# AC_Relay.net
KiCad netlist of a schematic drawn in Altium Designer
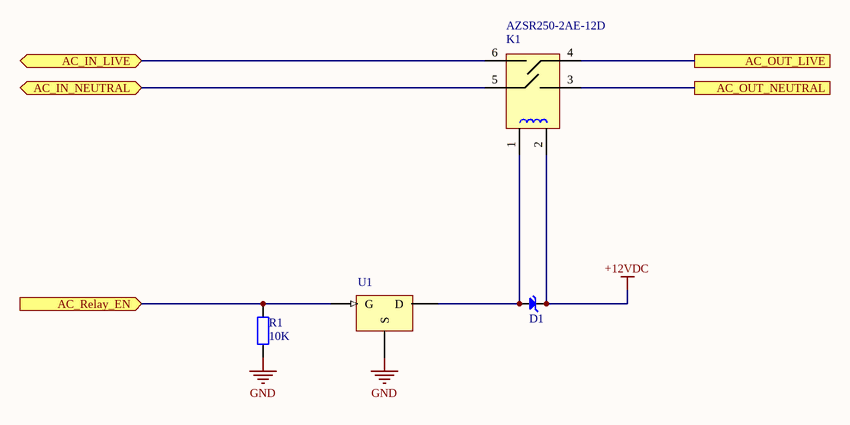
[diagram p0: AC_Relay.SchDoc]

(export (version "E")
  (design (tool "Eeschema 10.0.6"))
  (components
    (comp (ref "D1")
      (value "SMF16A")
      (footprint "SOD-123H")
      (description "Zener Diode")
      (fields (field (name "VOLTAGE") "16V") (field (name "MANUFACTURER") "Littelfuse Inc."))
      (libsource (lib "Database_library") (part "Zener_Diode"))
    )
    (comp (ref "K1")
      (value "AZSR250-2AE-12D")
      (footprint "AZSR250")
      (fields (field (name "MANUFACTURER") "American Zettler"))
      (libsource (lib "Database_library") (part "AZSR250"))
    )
    (comp (ref "R1")
      (value "10K")
      (footprint "RES 0603/1608")
      (description "RES SMD 10K OHM 1% 1/10W 0603")
      (fields (field (name "PART NUMBER") "RC0603FR-0710KL") (field (name "TOLERANCE") "±1%"))
      (libsource (lib "electric_racing_lib") (part "Resistor"))
    )
    (comp (ref "U1")
      (value "SZNUD3112LT1G")
      (footprint "SZNUD3112LT1G")
      (fields
        (field (name "PARTNUMBER") "SZNUD3112LT1GOSCT-ND")
        (field (name "MANUFACTURER") "ON Semiconductor")
      )
      (libsource (lib "Database_library") (part "SZNUD3112LT1G"))
    )
  )
  (nets
    (net (code "1") (name "+12VDC") (class "Default")
      (node (ref "D1") (pin "K") (pinfunction "K_K") (pintype "passive"))
      (node (ref "K1") (pin "2") (pintype "passive"))
    )
    (net (code "2") (name "/AC_IN_LIVE") (class "Default") (node (ref "K1") (pin "6") (pintype "passive")))
    (net (code "3") (name "/AC_IN_NEUTRAL") (class "Default") (node (ref "K1") (pin "5") (pintype "passive")))
    (net (code "4") (name "/AC_OUT_LIVE") (class "Default") (node (ref "K1") (pin "4") (pintype "passive")))
    (net (code "5") (name "/AC_OUT_NEUTRAL") (class "Default")
      (node (ref "K1") (pin "3") (pintype "passive"))
    )
    (net (code "6") (name "/AC_Relay_EN") (class "Default")
      (node (ref "R1") (pin "2") (pinfunction "2_2") (pintype "passive"))
      (node (ref "U1") (pin "1") (pinfunction "G_1") (pintype "input"))
    )
    (net (code "7") (name "GND") (class "Default")
      (node (ref "R1") (pin "1") (pinfunction "1_1") (pintype "passive"))
      (node (ref "U1") (pin "2") (pinfunction "S_2") (pintype "passive"))
    )
    (net (code "8") (name "Net-(U1-D)") (class "Default")
      (node (ref "D1") (pin "A") (pinfunction "A_A") (pintype "passive"))
      (node (ref "K1") (pin "1") (pintype "passive"))
      (node (ref "U1") (pin "3") (pinfunction "D_3") (pintype "passive"))
    )
  )
)
